# dasblinkenhat-controller-mk-4_0.net
KiCad netlist of a schematic drawn in EAGLE
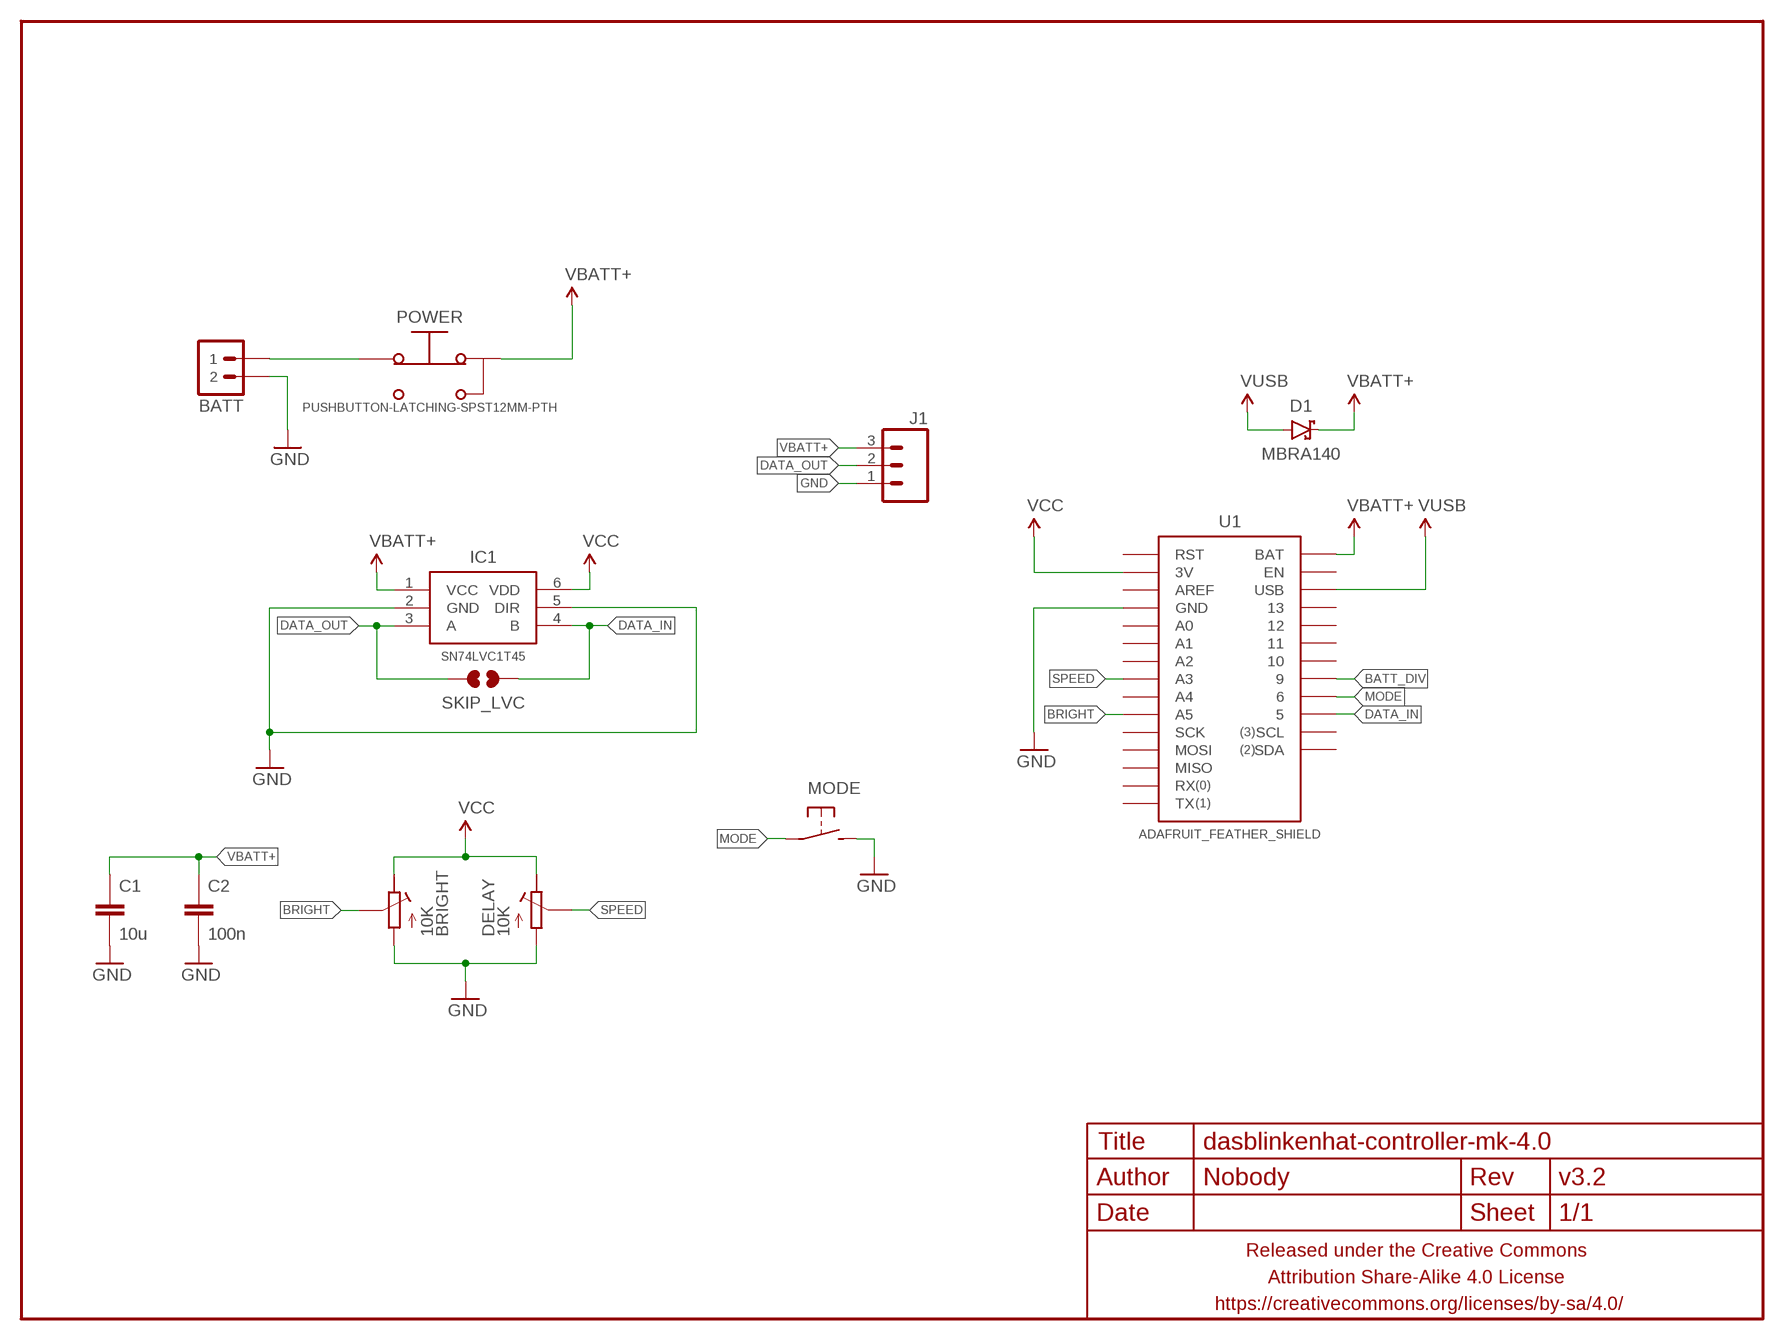
[diagram p0: schematic, sheet 1]

(export (version "E")
  (design (tool "Eeschema 10.0.6"))
  (components
    (comp (ref "BATT")
      (value "M02JST-2MM-SMT")
      (footprint "eagle-import:JST-2-SMD")
      (libsource (lib "eagle-import") (part "M02JST-2MM-SMT"))
    )
    (comp (ref "BRIGHT")
      (value "10K")
      (footprint "eagle-import:EVM3Y")
      (libsource (lib "eagle-import") (part "POTENTIOMETEREVM3Y"))
    )
    (comp (ref "C1")
      (value "10u")
      (footprint "eagle-import:C0805")
      (libsource (lib "eagle-import") (part "CAPACITOR-CERAMICC0805"))
    )
    (comp (ref "C2")
      (value "100n")
      (footprint "eagle-import:C0805")
      (libsource (lib "eagle-import") (part "CAPACITOR-CERAMICC0805"))
    )
    (comp (ref "D1")
      (value "MBRA140")
      (footprint "eagle-import:SMA-DIODE-SCHOTTKY")
      (libsource (lib "eagle-import") (part "DIODE-SCHOTTKYSMA"))
    )
    (comp (ref "DELAY")
      (value "10K")
      (footprint "eagle-import:EVM3Y")
      (libsource (lib "eagle-import") (part "POTENTIOMETEREVM3Y"))
    )
    (comp (ref "FRAME1")
      (value "FRAME-LETTERNO_PACKAGE")
      (footprint "eagle-import:DUMMY")
      (fields (field (name "VERSION") "v3.2") (field (name "DESIGNER") "Nobody"))
      (libsource (lib "eagle-import") (part "FRAME-LETTERNO_PACKAGE"))
    )
    (comp (ref "IC1")
      (value "SN74LVC1T45")
      (footprint "eagle-import:SOT23-6")
      (libsource (lib "eagle-import") (part "SN74LVC1T45SOT23-6"))
    )
    (comp (ref "J1")
      (value "M03JST-XH-RA-PTH")
      (footprint "eagle-import:JST-3-XH-RA-PTH")
      (libsource (lib "eagle-import") (part "M03JST-XH-RA-PTH"))
    )
    (comp (ref "MODE")
      (value "DTS-6MM")
      (footprint "eagle-import:DTSM-6")
      (libsource (lib "eagle-import") (part "SPST-NO-TACT6MM-SMD"))
    )
    (comp (ref "POWER")
      (value "PUSHBUTTON-LATCHING-SPST12MM-PTH")
      (footprint "eagle-import:PUSHBUTTON-CW-SPST-12MM")
      (libsource (lib "eagle-import") (part "PUSHBUTTON-LATCHING-SPST12MM-PTH"))
    )
    (comp (ref "SKIP_LVC")
      (value "JUMPER-PAD-2-NOYES_SILK")
      (footprint "eagle-import:PAD-JUMPER-2-NO_YES_SILK")
      (libsource (lib "eagle-import") (part "JUMPER-PAD-2-NOYES_SILK"))
    )
    (comp (ref "U1")
      (value "ADAFRUIT_FEATHER_SHIELD")
      (footprint "eagle-import:ADAFRUIT_FEATHER")
      (libsource (lib "eagle-import") (part "ADAFRUIT_FEATHER_SHIELD"))
    )
  )
  (nets
    (net (code "1") (name "BATT_DIV") (class "Default")
      (node (ref "U1") (pin "9") (pinfunction "9_9") (pintype "bidirectional"))
    )
    (net (code "2") (name "BRIGHT") (class "Default")
      (node (ref "BRIGHT") (pin "S") (pinfunction "S_S") (pintype "passive"))
      (node (ref "U1") (pin "A5") (pinfunction "A5_A5") (pintype "bidirectional"))
    )
    (net (code "3") (name "DATA_IN") (class "Default")
      (node (ref "IC1") (pin "4") (pinfunction "B_4") (pintype "bidirectional"))
      (node (ref "SKIP_LVC") (pin "1") (pinfunction "1_1") (pintype "passive"))
      (node (ref "U1") (pin "5") (pinfunction "5_5") (pintype "bidirectional"))
    )
    (net (code "4") (name "DATA_OUT") (class "Default")
      (node (ref "IC1") (pin "3") (pinfunction "A_3") (pintype "bidirectional"))
      (node (ref "J1") (pin "2") (pinfunction "2_2") (pintype "passive"))
      (node (ref "SKIP_LVC") (pin "2") (pinfunction "2_2") (pintype "passive"))
    )
    (net (code "5") (name "GND") (class "Default")
      (node (ref "BATT") (pin "1") (pinfunction "2_1") (pintype "passive"))
      (node (ref "BRIGHT") (pin "A") (pinfunction "A_A") (pintype "passive"))
      (node (ref "C1") (pin "2") (pinfunction "2_2") (pintype "passive"))
      (node (ref "C2") (pin "2") (pinfunction "2_2") (pintype "passive"))
      (node (ref "DELAY") (pin "A") (pinfunction "A_A") (pintype "passive"))
      (node (ref "IC1") (pin "2") (pinfunction "GND_2") (pintype "bidirectional"))
      (node (ref "IC1") (pin "5") (pinfunction "DIR_5") (pintype "bidirectional"))
      (node (ref "J1") (pin "1") (pinfunction "1_1") (pintype "passive"))
      (node (ref "MODE") (pin "3") (pinfunction "2_3") (pintype "passive"))
      (node (ref "MODE") (pin "4") (pinfunction "2_4") (pintype "passive"))
      (node (ref "U1") (pin "GND@0") (pinfunction "GND_GND@0") (pintype "bidirectional"))
      (node (ref "U1") (pin "GND@1") (pinfunction "GND_GND@1") (pintype "bidirectional"))
    )
    (net (code "6") (name "MODE") (class "Default")
      (node (ref "MODE") (pin "1") (pinfunction "1_1") (pintype "passive"))
      (node (ref "MODE") (pin "2") (pinfunction "1_2") (pintype "passive"))
      (node (ref "U1") (pin "6") (pinfunction "6_6") (pintype "bidirectional"))
    )
    (net (code "7") (name "Net-(BATT-1)") (class "Default")
      (node (ref "BATT") (pin "2") (pinfunction "1_2") (pintype "passive"))
      (node (ref "POWER") (pin "2") (pinfunction "NC_2") (pintype "bidirectional"))
    )
    (net (code "8") (name "SPEED") (class "Default")
      (node (ref "DELAY") (pin "S") (pinfunction "S_S") (pintype "passive"))
      (node (ref "U1") (pin "A3") (pinfunction "A3_A3") (pintype "bidirectional"))
    )
    (net (code "9") (name "VBATT+") (class "Default")
      (node (ref "C1") (pin "1") (pinfunction "1_1") (pintype "passive"))
      (node (ref "C2") (pin "1") (pinfunction "1_1") (pintype "passive"))
      (node (ref "D1") (pin "C") (pinfunction "C_C") (pintype "passive"))
      (node (ref "IC1") (pin "1") (pinfunction "VCC_1") (pintype "bidirectional"))
      (node (ref "J1") (pin "3") (pinfunction "3_3") (pintype "passive"))
      (node (ref "POWER") (pin "1") (pinfunction "COM_1") (pintype "bidirectional"))
      (node (ref "U1") (pin "BAT") (pinfunction "BAT_BAT") (pintype "bidirectional"))
    )
    (net (code "10") (name "VCC") (class "Default")
      (node (ref "BRIGHT") (pin "E") (pinfunction "E_E") (pintype "passive"))
      (node (ref "DELAY") (pin "E") (pinfunction "E_E") (pintype "passive"))
      (node (ref "IC1") (pin "6") (pinfunction "VDD_6") (pintype "bidirectional"))
      (node (ref "U1") (pin "3V") (pinfunction "3V_3V") (pintype "bidirectional"))
    )
    (net (code "11") (name "VUSB") (class "Default")
      (node (ref "D1") (pin "A") (pinfunction "A_A") (pintype "passive"))
      (node (ref "U1") (pin "USB") (pinfunction "USB_USB") (pintype "bidirectional"))
    )
    (net (code "12") (name "unconnected-(U1-Pad10)") (class "Default")
      (node (ref "U1") (pin "10") (pinfunction "10_10") (pintype "bidirectional"))
    )
    (net (code "13") (name "unconnected-(U1-Pad11)") (class "Default")
      (node (ref "U1") (pin "11") (pinfunction "11_11") (pintype "bidirectional"))
    )
    (net (code "14") (name "unconnected-(U1-Pad12)") (class "Default")
      (node (ref "U1") (pin "12") (pinfunction "12_12") (pintype "bidirectional"))
    )
    (net (code "15") (name "unconnected-(U1-Pad13)") (class "Default")
      (node (ref "U1") (pin "13") (pinfunction "13_13") (pintype "bidirectional"))
    )
    (net (code "16") (name "unconnected-(U1-PadA0)") (class "Default")
      (node (ref "U1") (pin "A0") (pinfunction "A0_A0") (pintype "bidirectional"))
    )
    (net (code "17") (name "unconnected-(U1-PadA1)") (class "Default")
      (node (ref "U1") (pin "A1") (pinfunction "A1_A1") (pintype "bidirectional"))
    )
    (net (code "18") (name "unconnected-(U1-PadA2)") (class "Default")
      (node (ref "U1") (pin "A2") (pinfunction "A2_A2") (pintype "bidirectional"))
    )
    (net (code "19") (name "unconnected-(U1-PadA4)") (class "Default")
      (node (ref "U1") (pin "A4") (pinfunction "A4_A4") (pintype "bidirectional"))
    )
    (net (code "20") (name "unconnected-(U1-PadAREF)") (class "Default")
      (node (ref "U1") (pin "AREF") (pinfunction "AREF_AREF") (pintype "bidirectional"))
    )
    (net (code "21") (name "unconnected-(U1-PadEN)") (class "Default")
      (node (ref "U1") (pin "EN") (pinfunction "EN_EN") (pintype "bidirectional"))
    )
    (net (code "22") (name "unconnected-(U1-PadMISO)") (class "Default")
      (node (ref "U1") (pin "MISO") (pinfunction "MISO_MISO") (pintype "bidirectional"))
    )
    (net (code "23") (name "unconnected-(U1-PadMOSI)") (class "Default")
      (node (ref "U1") (pin "MOSI") (pinfunction "MOSI_MOSI") (pintype "bidirectional"))
    )
    (net (code "24") (name "unconnected-(U1-PadRST)") (class "Default")
      (node (ref "U1") (pin "RST") (pinfunction "RST_RST") (pintype "bidirectional"))
    )
    (net (code "25") (name "unconnected-(U1-PadRX)") (class "Default")
      (node (ref "U1") (pin "RX") (pinfunction "RX_RX") (pintype "bidirectional"))
    )
    (net (code "26") (name "unconnected-(U1-PadSCK)") (class "Default")
      (node (ref "U1") (pin "SCK") (pinfunction "SCK_SCK") (pintype "bidirectional"))
    )
    (net (code "27") (name "unconnected-(U1-PadSCL)") (class "Default")
      (node (ref "U1") (pin "SCL") (pinfunction "SCL_SCL") (pintype "bidirectional"))
    )
    (net (code "28") (name "unconnected-(U1-PadSDA)") (class "Default")
      (node (ref "U1") (pin "SDA") (pinfunction "SDA_SDA") (pintype "bidirectional"))
    )
    (net (code "29") (name "unconnected-(U1-PadTX)") (class "Default")
      (node (ref "U1") (pin "TX") (pinfunction "TX_TX") (pintype "bidirectional"))
    )
  )
)
